# LED-board.net
KiCad netlist of a schematic drawn in EAGLE
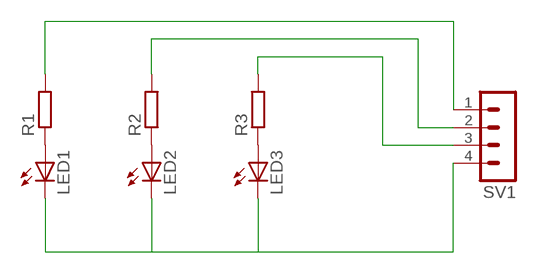
[diagram p0: schematic, sheet 1]

(export (version "E")
  (design (tool "Eeschema 10.0.6"))
  (components
    (comp (ref "LED1")
      (value "LED5MM")
      (footprint "eagle-import:LED5MM")
      (libsource (lib "eagle-import") (part "LED5MM"))
    )
    (comp (ref "LED2")
      (value "LED5MM")
      (footprint "eagle-import:LED5MM")
      (libsource (lib "eagle-import") (part "LED5MM"))
    )
    (comp (ref "LED3")
      (value "LED5MM")
      (footprint "eagle-import:LED5MM")
      (libsource (lib "eagle-import") (part "LED5MM"))
    )
    (comp (ref "R1")
      (value "R0207/10")
      (footprint "eagle-import:0207_10")
      (libsource (lib "eagle-import") (part "R0207/10"))
    )
    (comp (ref "R2")
      (value "R0207/10")
      (footprint "eagle-import:0207_10")
      (libsource (lib "eagle-import") (part "R0207/10"))
    )
    (comp (ref "R3")
      (value "R0207/10")
      (footprint "eagle-import:0207_10")
      (libsource (lib "eagle-import") (part "R0207/10"))
    )
    (comp (ref "SV1")
      (value "MA04-1")
      (footprint "eagle-import:MA04-1")
      (libsource (lib "eagle-import") (part "MA04-1"))
    )
  )
  (nets
    (net (code "1") (name "Net-(LED1-C)") (class "Default")
      (node (ref "LED1") (pin "K") (pinfunction "C_K") (pintype "passive"))
      (node (ref "LED2") (pin "K") (pinfunction "C_K") (pintype "passive"))
      (node (ref "LED3") (pin "K") (pinfunction "C_K") (pintype "passive"))
      (node (ref "SV1") (pin "4") (pinfunction "4_4") (pintype "passive"))
    )
    (net (code "2") (name "Net-(LED1-PadA)") (class "Default")
      (node (ref "LED1") (pin "A") (pinfunction "A_A") (pintype "passive"))
      (node (ref "R1") (pin "1") (pinfunction "1_1") (pintype "passive"))
    )
    (net (code "3") (name "Net-(LED2-PadA)") (class "Default")
      (node (ref "LED2") (pin "A") (pinfunction "A_A") (pintype "passive"))
      (node (ref "R2") (pin "1") (pinfunction "1_1") (pintype "passive"))
    )
    (net (code "4") (name "Net-(LED3-PadA)") (class "Default")
      (node (ref "LED3") (pin "A") (pinfunction "A_A") (pintype "passive"))
      (node (ref "R3") (pin "1") (pinfunction "1_1") (pintype "passive"))
    )
    (net (code "5") (name "Net-(R1-Pad2)") (class "Default")
      (node (ref "R1") (pin "2") (pinfunction "2_2") (pintype "passive"))
      (node (ref "SV1") (pin "1") (pinfunction "1_1") (pintype "passive"))
    )
    (net (code "6") (name "Net-(R2-Pad2)") (class "Default")
      (node (ref "R2") (pin "2") (pinfunction "2_2") (pintype "passive"))
      (node (ref "SV1") (pin "2") (pinfunction "2_2") (pintype "passive"))
    )
    (net (code "7") (name "Net-(R3-Pad2)") (class "Default")
      (node (ref "R3") (pin "2") (pinfunction "2_2") (pintype "passive"))
      (node (ref "SV1") (pin "3") (pinfunction "3_3") (pintype "passive"))
    )
  )
)
